# Board.net
KiCad netlist of a schematic drawn in Altium Designer
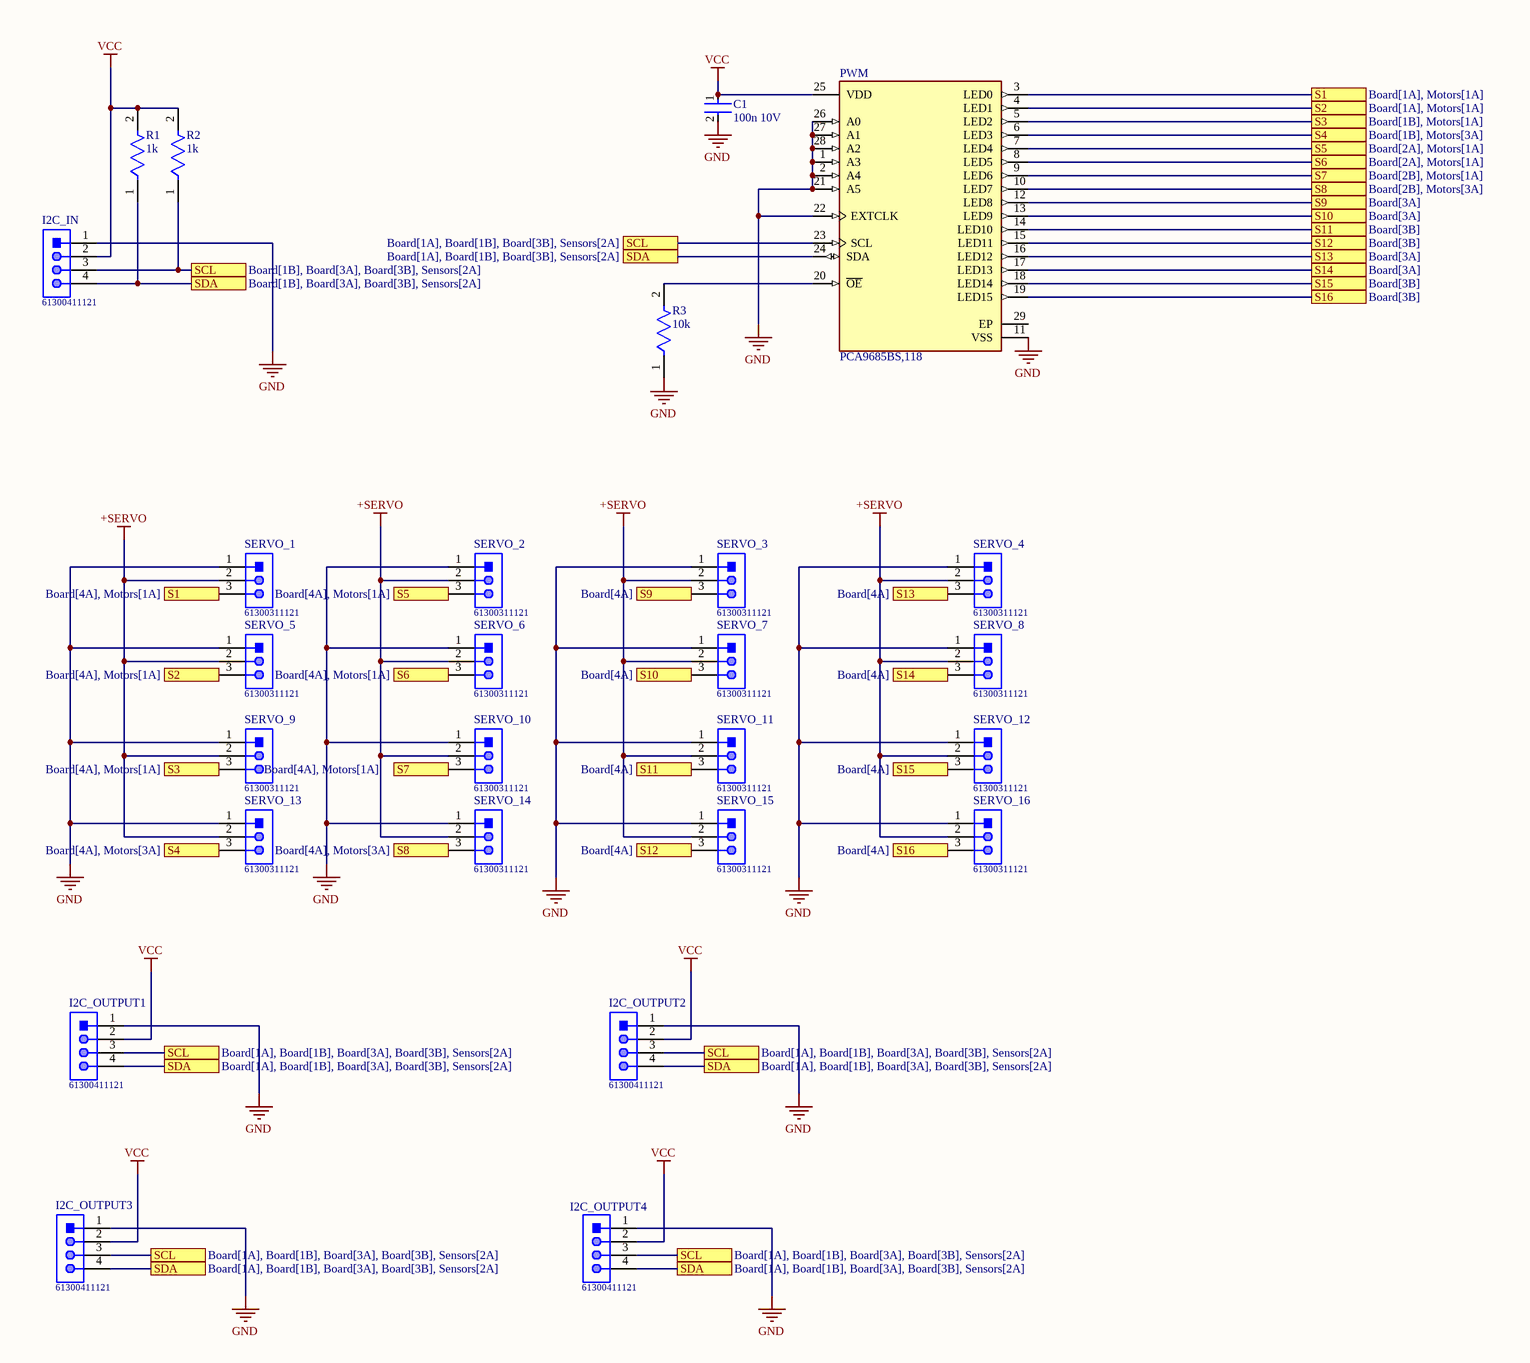
[diagram p0: Board.SchDoc]

(export (version "E")
  (design (tool "Eeschema 10.0.6"))
  (components
    (comp (ref "C1")
      (value "100n 10V")
      (footprint "FP-GRM155-0_05-MFG")
      (description "Chip Multilayer Ceramic Capacitors for General Purpose, 0402, 390pF, C0G, 30ppm/°C, 5%, 50V")
      (fields (field (name "TOLERANCE") "5%") (field (name "VOLTAGE") "50V"))
      (libsource (lib "Altium Content Vault") (part "02cd4be3c70576c341d710602a673aa"))
    )
    (comp (ref "I2C_IN")
      (value "61300411121")
      (footprint "61300411121")
      (description "THT Vertical Pin Header WR-PHD, Pitch 2.54 mm, Single Row, 4 pins")
      (fields (field (name "MANUFACTURER") "Wurth Elektronik") (field (name "PUBLISHER") "WurthElektronik"))
      (libsource (lib "Altium Content Vault") (part "WE-CN-1P-M-R4"))
    )
    (comp (ref "I2C_OUTPUT1")
      (value "61300411121")
      (footprint "61300411121")
      (description "THT Vertical Pin Header WR-PHD, Pitch 2.54 mm, Single Row, 4 pins")
      (fields (field (name "MANUFACTURER") "Wurth Elektronik") (field (name "PUBLISHER") "WurthElektronik"))
      (libsource (lib "Altium Content Vault") (part "WE-CN-1P-M-R4"))
    )
    (comp (ref "I2C_OUTPUT2")
      (value "61300411121")
      (footprint "61300411121")
      (description "THT Vertical Pin Header WR-PHD, Pitch 2.54 mm, Single Row, 4 pins")
      (fields (field (name "MANUFACTURER") "Wurth Elektronik") (field (name "PUBLISHER") "WurthElektronik"))
      (libsource (lib "Altium Content Vault") (part "WE-CN-1P-M-R4"))
    )
    (comp (ref "I2C_OUTPUT3")
      (value "61300411121")
      (footprint "61300411121")
      (description "THT Vertical Pin Header WR-PHD, Pitch 2.54 mm, Single Row, 4 pins")
      (fields (field (name "MANUFACTURER") "Wurth Elektronik") (field (name "PUBLISHER") "WurthElektronik"))
      (libsource (lib "Altium Content Vault") (part "WE-CN-1P-M-R4"))
    )
    (comp (ref "I2C_OUTPUT4")
      (value "61300411121")
      (footprint "61300411121")
      (description "THT Vertical Pin Header WR-PHD, Pitch 2.54 mm, Single Row, 4 pins")
      (fields (field (name "MANUFACTURER") "Wurth Elektronik") (field (name "PUBLISHER") "WurthElektronik"))
      (libsource (lib "Altium Content Vault") (part "WE-CN-1P-M-R4"))
    )
    (comp (ref "PWM")
      (value "PCA9685BS,118")
      (footprint "FP-SOT788-1-IPC_B")
      (description "IC LED DRVR LIN DIM 25MA 28HVQFN")
      (libsource (lib "Altium Content Vault") (part "09cd7da67ee680d27754e98215877c2"))
    )
    (comp (ref "R1")
      (value "1k")
      (footprint "FP-CRCW0402-e3-IPC_C")
      (description "RES Thick Film, 0Ω, 0.063W, 0402")
      (fields (field (name "TOLERANCE") "5%"))
      (libsource (lib "Altium Content Vault") (part "1029c3af85768c4190bb7ad29bc67b5"))
    )
    (comp (ref "R2")
      (value "1k")
      (footprint "FP-CRCW0402-e3-IPC_C")
      (description "RES Thick Film, 0Ω, 0.063W, 0402")
      (fields (field (name "TOLERANCE") "5%"))
      (libsource (lib "Altium Content Vault") (part "1029c3af85768c4190bb7ad29bc67b5"))
    )
    (comp (ref "R3")
      (value "10k")
      (footprint "FP-CRCW0402-e3-IPC_C")
      (description "RES Thick Film, 0Ω, 0.063W, 0402")
      (fields (field (name "TOLERANCE") "5%"))
      (libsource (lib "Altium Content Vault") (part "1029c3af85768c4190bb7ad29bc67b5"))
    )
    (comp (ref "SERVO_1")
      (value "61300311121")
      (footprint "61300311121")
      (description "THT Vertical Pin Header WR-PHD, Pitch 2.54 mm, Single Row, 3 pins")
      (fields (field (name "MANUFACTURER") "Wurth Elektronik") (field (name "PUBLISHER") "WurthElektronik"))
      (libsource (lib "Altium Content Vault") (part "WE-CN-1P-M-R3"))
    )
    (comp (ref "SERVO_2")
      (value "61300311121")
      (footprint "61300311121")
      (description "THT Vertical Pin Header WR-PHD, Pitch 2.54 mm, Single Row, 3 pins")
      (fields (field (name "MANUFACTURER") "Wurth Elektronik") (field (name "PUBLISHER") "WurthElektronik"))
      (libsource (lib "Altium Content Vault") (part "WE-CN-1P-M-R3"))
    )
    (comp (ref "SERVO_3")
      (value "61300311121")
      (footprint "61300311121")
      (description "THT Vertical Pin Header WR-PHD, Pitch 2.54 mm, Single Row, 3 pins")
      (fields (field (name "MANUFACTURER") "Wurth Elektronik") (field (name "PUBLISHER") "WurthElektronik"))
      (libsource (lib "Altium Content Vault") (part "WE-CN-1P-M-R3"))
    )
    (comp (ref "SERVO_4")
      (value "61300311121")
      (footprint "61300311121")
      (description "THT Vertical Pin Header WR-PHD, Pitch 2.54 mm, Single Row, 3 pins")
      (fields (field (name "MANUFACTURER") "Wurth Elektronik") (field (name "PUBLISHER") "WurthElektronik"))
      (libsource (lib "Altium Content Vault") (part "WE-CN-1P-M-R3"))
    )
    (comp (ref "SERVO_5")
      (value "61300311121")
      (footprint "61300311121")
      (description "THT Vertical Pin Header WR-PHD, Pitch 2.54 mm, Single Row, 3 pins")
      (fields (field (name "MANUFACTURER") "Wurth Elektronik") (field (name "PUBLISHER") "WurthElektronik"))
      (libsource (lib "Altium Content Vault") (part "WE-CN-1P-M-R3"))
    )
    (comp (ref "SERVO_6")
      (value "61300311121")
      (footprint "61300311121")
      (description "THT Vertical Pin Header WR-PHD, Pitch 2.54 mm, Single Row, 3 pins")
      (fields (field (name "MANUFACTURER") "Wurth Elektronik") (field (name "PUBLISHER") "WurthElektronik"))
      (libsource (lib "Altium Content Vault") (part "WE-CN-1P-M-R3"))
    )
    (comp (ref "SERVO_7")
      (value "61300311121")
      (footprint "61300311121")
      (description "THT Vertical Pin Header WR-PHD, Pitch 2.54 mm, Single Row, 3 pins")
      (fields (field (name "MANUFACTURER") "Wurth Elektronik") (field (name "PUBLISHER") "WurthElektronik"))
      (libsource (lib "Altium Content Vault") (part "WE-CN-1P-M-R3"))
    )
    (comp (ref "SERVO_8")
      (value "61300311121")
      (footprint "61300311121")
      (description "THT Vertical Pin Header WR-PHD, Pitch 2.54 mm, Single Row, 3 pins")
      (fields (field (name "MANUFACTURER") "Wurth Elektronik") (field (name "PUBLISHER") "WurthElektronik"))
      (libsource (lib "Altium Content Vault") (part "WE-CN-1P-M-R3"))
    )
    (comp (ref "SERVO_9")
      (value "61300311121")
      (footprint "61300311121")
      (description "THT Vertical Pin Header WR-PHD, Pitch 2.54 mm, Single Row, 3 pins")
      (fields (field (name "MANUFACTURER") "Wurth Elektronik") (field (name "PUBLISHER") "WurthElektronik"))
      (libsource (lib "Altium Content Vault") (part "WE-CN-1P-M-R3"))
    )
    (comp (ref "SERVO_10")
      (value "61300311121")
      (footprint "61300311121")
      (description "THT Vertical Pin Header WR-PHD, Pitch 2.54 mm, Single Row, 3 pins")
      (fields (field (name "MANUFACTURER") "Wurth Elektronik") (field (name "PUBLISHER") "WurthElektronik"))
      (libsource (lib "Altium Content Vault") (part "WE-CN-1P-M-R3"))
    )
    (comp (ref "SERVO_11")
      (value "61300311121")
      (footprint "61300311121")
      (description "THT Vertical Pin Header WR-PHD, Pitch 2.54 mm, Single Row, 3 pins")
      (fields (field (name "MANUFACTURER") "Wurth Elektronik") (field (name "PUBLISHER") "WurthElektronik"))
      (libsource (lib "Altium Content Vault") (part "WE-CN-1P-M-R3"))
    )
    (comp (ref "SERVO_12")
      (value "61300311121")
      (footprint "61300311121")
      (description "THT Vertical Pin Header WR-PHD, Pitch 2.54 mm, Single Row, 3 pins")
      (fields (field (name "MANUFACTURER") "Wurth Elektronik") (field (name "PUBLISHER") "WurthElektronik"))
      (libsource (lib "Altium Content Vault") (part "WE-CN-1P-M-R3"))
    )
    (comp (ref "SERVO_13")
      (value "61300311121")
      (footprint "61300311121")
      (description "THT Vertical Pin Header WR-PHD, Pitch 2.54 mm, Single Row, 3 pins")
      (fields (field (name "MANUFACTURER") "Wurth Elektronik") (field (name "PUBLISHER") "WurthElektronik"))
      (libsource (lib "Altium Content Vault") (part "WE-CN-1P-M-R3"))
    )
    (comp (ref "SERVO_14")
      (value "61300311121")
      (footprint "61300311121")
      (description "THT Vertical Pin Header WR-PHD, Pitch 2.54 mm, Single Row, 3 pins")
      (fields (field (name "MANUFACTURER") "Wurth Elektronik") (field (name "PUBLISHER") "WurthElektronik"))
      (libsource (lib "Altium Content Vault") (part "WE-CN-1P-M-R3"))
    )
    (comp (ref "SERVO_15")
      (value "61300311121")
      (footprint "61300311121")
      (description "THT Vertical Pin Header WR-PHD, Pitch 2.54 mm, Single Row, 3 pins")
      (fields (field (name "MANUFACTURER") "Wurth Elektronik") (field (name "PUBLISHER") "WurthElektronik"))
      (libsource (lib "Altium Content Vault") (part "WE-CN-1P-M-R3"))
    )
    (comp (ref "SERVO_16")
      (value "61300311121")
      (footprint "61300311121")
      (description "THT Vertical Pin Header WR-PHD, Pitch 2.54 mm, Single Row, 3 pins")
      (fields (field (name "MANUFACTURER") "Wurth Elektronik") (field (name "PUBLISHER") "WurthElektronik"))
      (libsource (lib "Altium Content Vault") (part "WE-CN-1P-M-R3"))
    )
  )
  (nets
    (net (code "1") (name "+SERVO") (class "Default")
      (node (ref "SERVO_1") (pin "2") (pinfunction "2_2") (pintype "passive"))
      (node (ref "SERVO_10") (pin "2") (pinfunction "2_2") (pintype "passive"))
      (node (ref "SERVO_11") (pin "2") (pinfunction "2_2") (pintype "passive"))
      (node (ref "SERVO_12") (pin "2") (pinfunction "2_2") (pintype "passive"))
      (node (ref "SERVO_13") (pin "2") (pinfunction "2_2") (pintype "passive"))
      (node (ref "SERVO_14") (pin "2") (pinfunction "2_2") (pintype "passive"))
      (node (ref "SERVO_15") (pin "2") (pinfunction "2_2") (pintype "passive"))
      (node (ref "SERVO_16") (pin "2") (pinfunction "2_2") (pintype "passive"))
      (node (ref "SERVO_2") (pin "2") (pinfunction "2_2") (pintype "passive"))
      (node (ref "SERVO_3") (pin "2") (pinfunction "2_2") (pintype "passive"))
      (node (ref "SERVO_4") (pin "2") (pinfunction "2_2") (pintype "passive"))
      (node (ref "SERVO_5") (pin "2") (pinfunction "2_2") (pintype "passive"))
      (node (ref "SERVO_6") (pin "2") (pinfunction "2_2") (pintype "passive"))
      (node (ref "SERVO_7") (pin "2") (pinfunction "2_2") (pintype "passive"))
      (node (ref "SERVO_8") (pin "2") (pinfunction "2_2") (pintype "passive"))
      (node (ref "SERVO_9") (pin "2") (pinfunction "2_2") (pintype "passive"))
    )
    (net (code "2") (name "/S1") (class "Default")
      (node (ref "PWM") (pin "3") (pinfunction "LED0_3") (pintype "output"))
      (node (ref "SERVO_1") (pin "3") (pinfunction "3_3") (pintype "passive"))
    )
    (net (code "3") (name "/S2") (class "Default")
      (node (ref "PWM") (pin "4") (pinfunction "LED1_4") (pintype "output"))
      (node (ref "SERVO_5") (pin "3") (pinfunction "3_3") (pintype "passive"))
    )
    (net (code "4") (name "/S3") (class "Default")
      (node (ref "PWM") (pin "5") (pinfunction "LED2_5") (pintype "output"))
      (node (ref "SERVO_9") (pin "3") (pinfunction "3_3") (pintype "passive"))
    )
    (net (code "5") (name "/S4") (class "Default")
      (node (ref "PWM") (pin "6") (pinfunction "LED3_6") (pintype "output"))
      (node (ref "SERVO_13") (pin "3") (pinfunction "3_3") (pintype "passive"))
    )
    (net (code "6") (name "/S5") (class "Default")
      (node (ref "PWM") (pin "7") (pinfunction "LED4_7") (pintype "output"))
      (node (ref "SERVO_2") (pin "3") (pinfunction "3_3") (pintype "passive"))
    )
    (net (code "7") (name "/S6") (class "Default")
      (node (ref "PWM") (pin "8") (pinfunction "LED5_8") (pintype "output"))
      (node (ref "SERVO_6") (pin "3") (pinfunction "3_3") (pintype "passive"))
    )
    (net (code "8") (name "/S7") (class "Default")
      (node (ref "PWM") (pin "9") (pinfunction "LED6_9") (pintype "output"))
      (node (ref "SERVO_10") (pin "3") (pinfunction "3_3") (pintype "passive"))
    )
    (net (code "9") (name "/S8") (class "Default")
      (node (ref "PWM") (pin "10") (pinfunction "LED7_10") (pintype "output"))
      (node (ref "SERVO_14") (pin "3") (pinfunction "3_3") (pintype "passive"))
    )
    (net (code "10") (name "/S9") (class "Default")
      (node (ref "PWM") (pin "12") (pinfunction "LED8_12") (pintype "output"))
      (node (ref "SERVO_3") (pin "3") (pinfunction "3_3") (pintype "passive"))
    )
    (net (code "11") (name "/S10") (class "Default")
      (node (ref "PWM") (pin "13") (pinfunction "LED9_13") (pintype "output"))
      (node (ref "SERVO_7") (pin "3") (pinfunction "3_3") (pintype "passive"))
    )
    (net (code "12") (name "/S11") (class "Default")
      (node (ref "PWM") (pin "14") (pinfunction "LED10_14") (pintype "output"))
      (node (ref "SERVO_11") (pin "3") (pinfunction "3_3") (pintype "passive"))
    )
    (net (code "13") (name "/S12") (class "Default")
      (node (ref "PWM") (pin "15") (pinfunction "LED11_15") (pintype "output"))
      (node (ref "SERVO_15") (pin "3") (pinfunction "3_3") (pintype "passive"))
    )
    (net (code "14") (name "/S13") (class "Default")
      (node (ref "PWM") (pin "16") (pinfunction "LED12_16") (pintype "output"))
      (node (ref "SERVO_4") (pin "3") (pinfunction "3_3") (pintype "passive"))
    )
    (net (code "15") (name "/S14") (class "Default")
      (node (ref "PWM") (pin "17") (pinfunction "LED13_17") (pintype "output"))
      (node (ref "SERVO_8") (pin "3") (pinfunction "3_3") (pintype "passive"))
    )
    (net (code "16") (name "/S15") (class "Default")
      (node (ref "PWM") (pin "18") (pinfunction "LED14_18") (pintype "output"))
      (node (ref "SERVO_12") (pin "3") (pinfunction "3_3") (pintype "passive"))
    )
    (net (code "17") (name "/S16") (class "Default")
      (node (ref "PWM") (pin "19") (pinfunction "LED15_19") (pintype "output"))
      (node (ref "SERVO_16") (pin "3") (pinfunction "3_3") (pintype "passive"))
    )
    (net (code "18") (name "/SCL") (class "Default")
      (node (ref "I2C_IN") (pin "3") (pinfunction "3_3") (pintype "passive"))
      (node (ref "I2C_OUTPUT1") (pin "3") (pinfunction "3_3") (pintype "passive"))
      (node (ref "I2C_OUTPUT2") (pin "3") (pinfunction "3_3") (pintype "passive"))
      (node (ref "I2C_OUTPUT3") (pin "3") (pinfunction "3_3") (pintype "passive"))
      (node (ref "I2C_OUTPUT4") (pin "3") (pinfunction "3_3") (pintype "passive"))
      (node (ref "PWM") (pin "23") (pinfunction "SCL_23") (pintype "input"))
      (node (ref "R2") (pin "1") (pinfunction "1_1") (pintype "passive"))
    )
    (net (code "19") (name "/SDA") (class "Default")
      (node (ref "I2C_IN") (pin "4") (pinfunction "4_4") (pintype "passive"))
      (node (ref "I2C_OUTPUT1") (pin "4") (pinfunction "4_4") (pintype "passive"))
      (node (ref "I2C_OUTPUT2") (pin "4") (pinfunction "4_4") (pintype "passive"))
      (node (ref "I2C_OUTPUT3") (pin "4") (pinfunction "4_4") (pintype "passive"))
      (node (ref "I2C_OUTPUT4") (pin "4") (pinfunction "4_4") (pintype "passive"))
      (node (ref "PWM") (pin "24") (pinfunction "SDA_24") (pintype "bidirectional"))
      (node (ref "R1") (pin "1") (pinfunction "1_1") (pintype "passive"))
    )
    (net (code "20") (name "GND") (class "Default")
      (node (ref "C1") (pin "2") (pinfunction "2_2") (pintype "passive"))
      (node (ref "I2C_IN") (pin "1") (pinfunction "1_1") (pintype "passive"))
      (node (ref "I2C_OUTPUT1") (pin "1") (pinfunction "1_1") (pintype "passive"))
      (node (ref "I2C_OUTPUT2") (pin "1") (pinfunction "1_1") (pintype "passive"))
      (node (ref "I2C_OUTPUT3") (pin "1") (pinfunction "1_1") (pintype "passive"))
      (node (ref "I2C_OUTPUT4") (pin "1") (pinfunction "1_1") (pintype "passive"))
      (node (ref "PWM") (pin "1") (pinfunction "A3_1") (pintype "input"))
      (node (ref "PWM") (pin "11") (pinfunction "VSS_11") (pintype "power_in"))
      (node (ref "PWM") (pin "2") (pinfunction "A4_2") (pintype "input"))
      (node (ref "PWM") (pin "21") (pinfunction "A5_21") (pintype "input"))
      (node (ref "PWM") (pin "22") (pinfunction "EXTCLK_22") (pintype "input"))
      (node (ref "PWM") (pin "26") (pinfunction "A0_26") (pintype "input"))
      (node (ref "PWM") (pin "27") (pinfunction "A1_27") (pintype "input"))
      (node (ref "PWM") (pin "28") (pinfunction "A2_28") (pintype "input"))
      (node (ref "R3") (pin "1") (pinfunction "1_1") (pintype "passive"))
      (node (ref "SERVO_1") (pin "1") (pinfunction "1_1") (pintype "passive"))
      (node (ref "SERVO_10") (pin "1") (pinfunction "1_1") (pintype "passive"))
      (node (ref "SERVO_11") (pin "1") (pinfunction "1_1") (pintype "passive"))
      (node (ref "SERVO_12") (pin "1") (pinfunction "1_1") (pintype "passive"))
      (node (ref "SERVO_13") (pin "1") (pinfunction "1_1") (pintype "passive"))
      (node (ref "SERVO_14") (pin "1") (pinfunction "1_1") (pintype "passive"))
      (node (ref "SERVO_15") (pin "1") (pinfunction "1_1") (pintype "passive"))
      (node (ref "SERVO_16") (pin "1") (pinfunction "1_1") (pintype "passive"))
      (node (ref "SERVO_2") (pin "1") (pinfunction "1_1") (pintype "passive"))
      (node (ref "SERVO_3") (pin "1") (pinfunction "1_1") (pintype "passive"))
      (node (ref "SERVO_4") (pin "1") (pinfunction "1_1") (pintype "passive"))
      (node (ref "SERVO_5") (pin "1") (pinfunction "1_1") (pintype "passive"))
      (node (ref "SERVO_6") (pin "1") (pinfunction "1_1") (pintype "passive"))
      (node (ref "SERVO_7") (pin "1") (pinfunction "1_1") (pintype "passive"))
      (node (ref "SERVO_8") (pin "1") (pinfunction "1_1") (pintype "passive"))
      (node (ref "SERVO_9") (pin "1") (pinfunction "1_1") (pintype "passive"))
    )
    (net (code "21") (name "Net-(PWM-~{OE})") (class "Default")
      (node (ref "PWM") (pin "20") (pinfunction "~{OE}_20") (pintype "input"))
      (node (ref "R3") (pin "2") (pinfunction "2_2") (pintype "passive"))
    )
    (net (code "22") (name "VCC") (class "Default")
      (node (ref "C1") (pin "1") (pinfunction "1_1") (pintype "passive"))
      (node (ref "I2C_IN") (pin "2") (pinfunction "2_2") (pintype "passive"))
      (node (ref "I2C_OUTPUT1") (pin "2") (pinfunction "2_2") (pintype "passive"))
      (node (ref "I2C_OUTPUT2") (pin "2") (pinfunction "2_2") (pintype "passive"))
      (node (ref "I2C_OUTPUT3") (pin "2") (pinfunction "2_2") (pintype "passive"))
      (node (ref "I2C_OUTPUT4") (pin "2") (pinfunction "2_2") (pintype "passive"))
      (node (ref "PWM") (pin "25") (pinfunction "VDD_25") (pintype "power_in"))
      (node (ref "R1") (pin "2") (pinfunction "2_2") (pintype "passive"))
      (node (ref "R2") (pin "2") (pinfunction "2_2") (pintype "passive"))
    )
    (net (code "23") (name "unconnected-(PWM-EP-Pad29)") (class "Default")
      (node (ref "PWM") (pin "29") (pinfunction "EP_29") (pintype "passive"))
    )
  )
)
